# rf-temperature-sensor.net
KiCad netlist of a schematic drawn in EAGLE
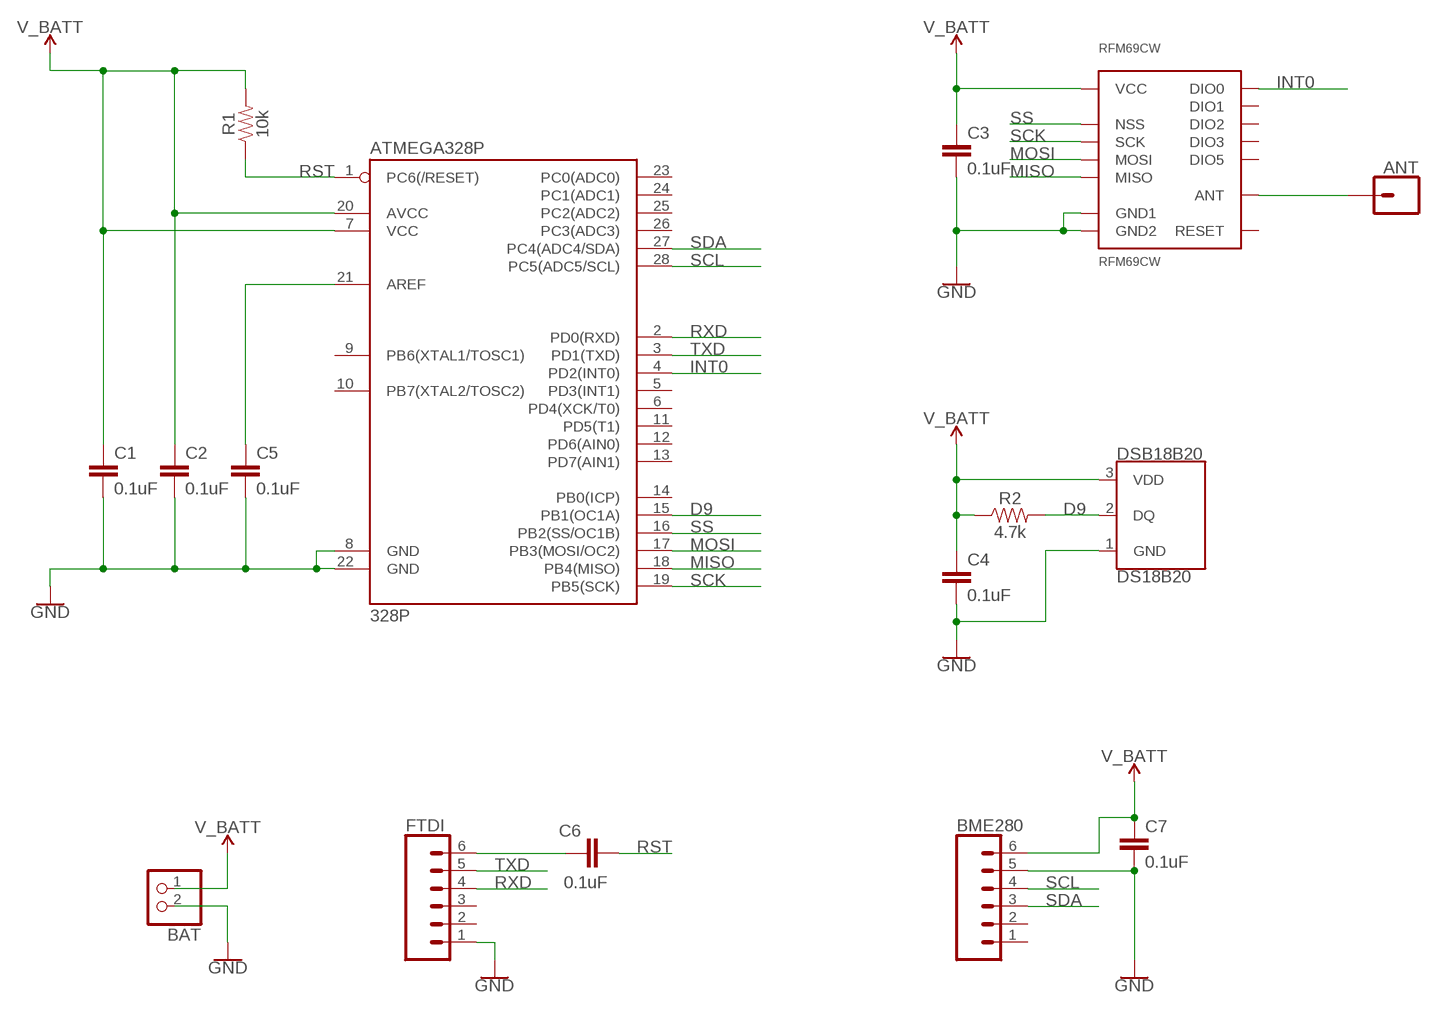
[diagram p0: schematic, sheet 1]

(export (version "E")
  (design (tool "Eeschema 10.0.6"))
  (components
    (comp (ref "ANT")
      (value "CONN_01")
      (footprint "eagle-import:1X01")
      (libsource (lib "eagle-import") (part "CONN_01"))
    )
    (comp (ref "ATMEGA328P")
      (value "328P")
      (footprint "eagle-import:DIP28")
      (libsource (lib "eagle-import") (part "ATMEGA328P_PDIP"))
    )
    (comp (ref "BAT")
      (value "JST_2PIN-THM-RA")
      (footprint "eagle-import:JST-PH-2-THM-RA")
      (libsource (lib "eagle-import") (part "JST_2PIN-THM-RA"))
    )
    (comp (ref "BME280")
      (value "CONN_06SILK_FEMALE_PTH")
      (footprint "eagle-import:1X06")
      (libsource (lib "eagle-import") (part "CONN_06SILK_FEMALE_PTH"))
    )
    (comp (ref "C1")
      (value "0.1uF")
      (footprint "eagle-import:0603")
      (libsource (lib "eagle-import") (part "0.1UF-0603-25V-5%"))
    )
    (comp (ref "C2")
      (value "0.1uF")
      (footprint "eagle-import:0603")
      (libsource (lib "eagle-import") (part "0.1UF-0603-25V-5%"))
    )
    (comp (ref "C3")
      (value "0.1uF")
      (footprint "eagle-import:0603")
      (libsource (lib "eagle-import") (part "0.1UF-0603-25V-5%"))
    )
    (comp (ref "C4")
      (value "0.1uF")
      (footprint "eagle-import:0603")
      (libsource (lib "eagle-import") (part "0.1UF-0603-25V-5%"))
    )
    (comp (ref "C5")
      (value "0.1uF")
      (footprint "eagle-import:0603")
      (libsource (lib "eagle-import") (part "0.1UF-0603-25V-5%"))
    )
    (comp (ref "C6")
      (value "0.1uF")
      (footprint "eagle-import:0603")
      (libsource (lib "eagle-import") (part "0.1UF-0603-25V-5%"))
    )
    (comp (ref "C7")
      (value "0.1uF")
      (footprint "eagle-import:0603")
      (libsource (lib "eagle-import") (part "0.1UF-0603-25V-5%"))
    )
    (comp (ref "DSB18B20")
      (value "DS18B20")
      (footprint "eagle-import:TO-92-AMMO")
      (libsource (lib "eagle-import") (part "DS18B20"))
    )
    (comp (ref "FTDI")
      (value "CONN_06SILK_FEMALE_PTH")
      (footprint "eagle-import:1X06")
      (libsource (lib "eagle-import") (part "CONN_06SILK_FEMALE_PTH"))
    )
    (comp (ref "R1")
      (value "10k")
      (footprint "eagle-import:0603")
      (libsource (lib "eagle-import") (part "10KOHM-0603-1/10W-1%"))
    )
    (comp (ref "R2")
      (value "4.7k")
      (footprint "eagle-import:0603")
      (libsource (lib "eagle-import") (part "4.7KOHM-0603-1/10W-1%"))
    )
    (comp (ref "RFM69CW")
      (value "RFM69CW")
      (footprint "eagle-import:RFM69CW")
      (libsource (lib "eagle-import") (part "RFM69CW"))
    )
  )
  (nets
    (net (code "1") (name "/D9") (class "Default")
      (node (ref "ATMEGA328P") (pin "15") (pinfunction "PB1(OC1A)_15") (pintype "bidirectional"))
      (node (ref "DSB18B20") (pin "2") (pinfunction "DQ_2") (pintype "bidirectional"))
      (node (ref "R2") (pin "2") (pinfunction "2_2") (pintype "passive"))
    )
    (net (code "2") (name "/INT0") (class "Default")
      (node (ref "ATMEGA328P") (pin "4") (pinfunction "PD2(INT0)_4") (pintype "bidirectional"))
      (node (ref "RFM69CW") (pin "DIO0") (pinfunction "DIO0_DIO0") (pintype "open_collector"))
    )
    (net (code "3") (name "/MISO") (class "Default")
      (node (ref "ATMEGA328P") (pin "18") (pinfunction "PB4(MISO)_18") (pintype "bidirectional"))
      (node (ref "RFM69CW") (pin "MISO") (pinfunction "MISO_MISO") (pintype "output"))
    )
    (net (code "4") (name "/MOSI") (class "Default")
      (node (ref "ATMEGA328P") (pin "17") (pinfunction "PB3(MOSI/OC2)_17") (pintype "bidirectional"))
      (node (ref "RFM69CW") (pin "MOSI") (pinfunction "MOSI_MOSI") (pintype "input"))
    )
    (net (code "5") (name "/RST") (class "Default")
      (node (ref "ATMEGA328P") (pin "1") (pinfunction "PC6(/RESET)_1") (pintype "bidirectional"))
      (node (ref "C6") (pin "2") (pinfunction "2_2") (pintype "passive"))
      (node (ref "R1") (pin "1") (pinfunction "1_1") (pintype "passive"))
    )
    (net (code "6") (name "/RXD") (class "Default")
      (node (ref "ATMEGA328P") (pin "2") (pinfunction "PD0(RXD)_2") (pintype "bidirectional"))
      (node (ref "FTDI") (pin "4") (pinfunction "4_4") (pintype "passive"))
    )
    (net (code "7") (name "/SCK") (class "Default")
      (node (ref "ATMEGA328P") (pin "19") (pinfunction "PB5(SCK)_19") (pintype "bidirectional"))
      (node (ref "RFM69CW") (pin "SCK") (pinfunction "SCK_SCK") (pintype "input"))
    )
    (net (code "8") (name "/SCL") (class "Default")
      (node (ref "ATMEGA328P") (pin "28") (pinfunction "PC5(ADC5/SCL)_28") (pintype "bidirectional"))
      (node (ref "BME280") (pin "4") (pinfunction "4_4") (pintype "passive"))
    )
    (net (code "9") (name "/SDA") (class "Default")
      (node (ref "ATMEGA328P") (pin "27") (pinfunction "PC4(ADC4/SDA)_27") (pintype "bidirectional"))
      (node (ref "BME280") (pin "3") (pinfunction "3_3") (pintype "passive"))
    )
    (net (code "10") (name "/SS") (class "Default")
      (node (ref "ATMEGA328P") (pin "16") (pinfunction "PB2(SS/OC1B)_16") (pintype "bidirectional"))
      (node (ref "RFM69CW") (pin "NSS") (pinfunction "NSS_NSS") (pintype "input"))
    )
    (net (code "11") (name "/TXD") (class "Default")
      (node (ref "ATMEGA328P") (pin "3") (pinfunction "PD1(TXD)_3") (pintype "bidirectional"))
      (node (ref "FTDI") (pin "5") (pinfunction "5_5") (pintype "passive"))
    )
    (net (code "12") (name "GND") (class "Default")
      (node (ref "ATMEGA328P") (pin "22") (pinfunction "GND_22") (pintype "bidirectional"))
      (node (ref "ATMEGA328P") (pin "8") (pinfunction "GND_8") (pintype "bidirectional"))
      (node (ref "BAT") (pin "2") (pinfunction "1_2") (pintype "passive"))
      (node (ref "BME280") (pin "5") (pinfunction "5_5") (pintype "passive"))
      (node (ref "C1") (pin "2") (pinfunction "2_2") (pintype "passive"))
      (node (ref "C2") (pin "2") (pinfunction "2_2") (pintype "passive"))
      (node (ref "C3") (pin "2") (pinfunction "2_2") (pintype "passive"))
      (node (ref "C4") (pin "2") (pinfunction "2_2") (pintype "passive"))
      (node (ref "C5") (pin "2") (pinfunction "2_2") (pintype "passive"))
      (node (ref "C7") (pin "2") (pinfunction "2_2") (pintype "passive"))
      (node (ref "DSB18B20") (pin "1") (pinfunction "GND_1") (pintype "power_in"))
      (node (ref "FTDI") (pin "1") (pinfunction "1_1") (pintype "passive"))
      (node (ref "RFM69CW") (pin "GND@1") (pinfunction "GND1_GND@1") (pintype "power_in"))
      (node (ref "RFM69CW") (pin "GND@2") (pinfunction "GND2_GND@2") (pintype "power_in"))
    )
    (net (code "13") (name "Net-(ANT-Pad1)") (class "Default")
      (node (ref "ANT") (pin "1") (pinfunction "1_1") (pintype "passive"))
      (node (ref "RFM69CW") (pin "ANT") (pinfunction "ANT_ANT") (pintype "passive"))
    )
    (net (code "14") (name "Net-(ATMEGA328P-AREF)") (class "Default")
      (node (ref "ATMEGA328P") (pin "21") (pinfunction "AREF_21") (pintype "bidirectional"))
      (node (ref "C5") (pin "1") (pinfunction "1_1") (pintype "passive"))
    )
    (net (code "15") (name "Net-(C6-Pad1)") (class "Default")
      (node (ref "C6") (pin "1") (pinfunction "1_1") (pintype "passive"))
      (node (ref "FTDI") (pin "6") (pinfunction "6_6") (pintype "passive"))
    )
    (net (code "16") (name "V_BATT") (class "Default")
      (node (ref "ATMEGA328P") (pin "20") (pinfunction "AVCC_20") (pintype "bidirectional"))
      (node (ref "ATMEGA328P") (pin "7") (pinfunction "VCC_7") (pintype "bidirectional"))
      (node (ref "BAT") (pin "1") (pinfunction "2_1") (pintype "passive"))
      (node (ref "BME280") (pin "6") (pinfunction "6_6") (pintype "passive"))
      (node (ref "C1") (pin "1") (pinfunction "1_1") (pintype "passive"))
      (node (ref "C2") (pin "1") (pinfunction "1_1") (pintype "passive"))
      (node (ref "C3") (pin "1") (pinfunction "1_1") (pintype "passive"))
      (node (ref "C4") (pin "1") (pinfunction "1_1") (pintype "passive"))
      (node (ref "C7") (pin "1") (pinfunction "1_1") (pintype "passive"))
      (node (ref "DSB18B20") (pin "3") (pinfunction "VDD_3") (pintype "power_in"))
      (node (ref "R1") (pin "2") (pinfunction "2_2") (pintype "passive"))
      (node (ref "R2") (pin "1") (pinfunction "1_1") (pintype "passive"))
      (node (ref "RFM69CW") (pin "VDD") (pinfunction "VCC_VDD") (pintype "power_in"))
    )
    (net (code "17") (name "unconnected-(ATMEGA328P-PB0(ICP)-Pad14)") (class "Default")
      (node (ref "ATMEGA328P") (pin "14") (pinfunction "PB0(ICP)_14") (pintype "bidirectional"))
    )
    (net (code "18") (name "unconnected-(ATMEGA328P-PB6(XTAL1{slash}TOSC1)-Pad9)") (class "Default")
      (node (ref "ATMEGA328P") (pin "9") (pinfunction "PB6(XTAL1/TOSC1)_9") (pintype "bidirectional"))
    )
    (net (code "19") (name "unconnected-(ATMEGA328P-PB7(XTAL2{slash}TOSC2)-Pad10)") (class "Default")
      (node (ref "ATMEGA328P") (pin "10") (pinfunction "PB7(XTAL2/TOSC2)_10") (pintype "bidirectional"))
    )
    (net (code "20") (name "unconnected-(ATMEGA328P-PC0(ADC0)-Pad23)") (class "Default")
      (node (ref "ATMEGA328P") (pin "23") (pinfunction "PC0(ADC0)_23") (pintype "bidirectional"))
    )
    (net (code "21") (name "unconnected-(ATMEGA328P-PC1(ADC1)-Pad24)") (class "Default")
      (node (ref "ATMEGA328P") (pin "24") (pinfunction "PC1(ADC1)_24") (pintype "bidirectional"))
    )
    (net (code "22") (name "unconnected-(ATMEGA328P-PC2(ADC2)-Pad25)") (class "Default")
      (node (ref "ATMEGA328P") (pin "25") (pinfunction "PC2(ADC2)_25") (pintype "bidirectional"))
    )
    (net (code "23") (name "unconnected-(ATMEGA328P-PC3(ADC3)-Pad26)") (class "Default")
      (node (ref "ATMEGA328P") (pin "26") (pinfunction "PC3(ADC3)_26") (pintype "bidirectional"))
    )
    (net (code "24") (name "unconnected-(ATMEGA328P-PD3(INT1)-Pad5)") (class "Default")
      (node (ref "ATMEGA328P") (pin "5") (pinfunction "PD3(INT1)_5") (pintype "bidirectional"))
    )
    (net (code "25") (name "unconnected-(ATMEGA328P-PD4(XCK{slash}T0)-Pad6)") (class "Default")
      (node (ref "ATMEGA328P") (pin "6") (pinfunction "PD4(XCK/T0)_6") (pintype "bidirectional"))
    )
    (net (code "26") (name "unconnected-(ATMEGA328P-PD5(T1)-Pad11)") (class "Default")
      (node (ref "ATMEGA328P") (pin "11") (pinfunction "PD5(T1)_11") (pintype "bidirectional"))
    )
    (net (code "27") (name "unconnected-(ATMEGA328P-PD6(AIN0)-Pad12)") (class "Default")
      (node (ref "ATMEGA328P") (pin "12") (pinfunction "PD6(AIN0)_12") (pintype "bidirectional"))
    )
    (net (code "28") (name "unconnected-(ATMEGA328P-PD7(AIN1)-Pad13)") (class "Default")
      (node (ref "ATMEGA328P") (pin "13") (pinfunction "PD7(AIN1)_13") (pintype "bidirectional"))
    )
    (net (code "29") (name "unconnected-(BME280-Pad1)") (class "Default")
      (node (ref "BME280") (pin "1") (pinfunction "1_1") (pintype "passive"))
    )
    (net (code "30") (name "unconnected-(BME280-Pad2)") (class "Default")
      (node (ref "BME280") (pin "2") (pinfunction "2_2") (pintype "passive"))
    )
    (net (code "31") (name "unconnected-(FTDI-Pad2)") (class "Default")
      (node (ref "FTDI") (pin "2") (pinfunction "2_2") (pintype "passive"))
    )
    (net (code "32") (name "unconnected-(FTDI-Pad3)") (class "Default")
      (node (ref "FTDI") (pin "3") (pinfunction "3_3") (pintype "passive"))
    )
    (net (code "33") (name "unconnected-(RFM69CW-PadDIO1)") (class "Default")
      (node (ref "RFM69CW") (pin "DIO1") (pinfunction "DIO1_DIO1") (pintype "bidirectional"))
    )
    (net (code "34") (name "unconnected-(RFM69CW-PadDIO2)") (class "Default")
      (node (ref "RFM69CW") (pin "DIO2") (pinfunction "DIO2_DIO2") (pintype "bidirectional"))
    )
    (net (code "35") (name "unconnected-(RFM69CW-PadDIO3)") (class "Default")
      (node (ref "RFM69CW") (pin "DIO3") (pinfunction "DIO3_DIO3") (pintype "bidirectional"))
    )
    (net (code "36") (name "unconnected-(RFM69CW-PadDIO5)") (class "Default")
      (node (ref "RFM69CW") (pin "DIO5") (pinfunction "DIO5_DIO5") (pintype "bidirectional"))
    )
    (net (code "37") (name "unconnected-(RFM69CW-PadRESET)") (class "Default")
      (node (ref "RFM69CW") (pin "RESET") (pinfunction "RESET_RESET") (pintype "bidirectional"))
    )
  )
)
